# breakout-a-bit.net
KiCad netlist of a schematic drawn in EAGLE
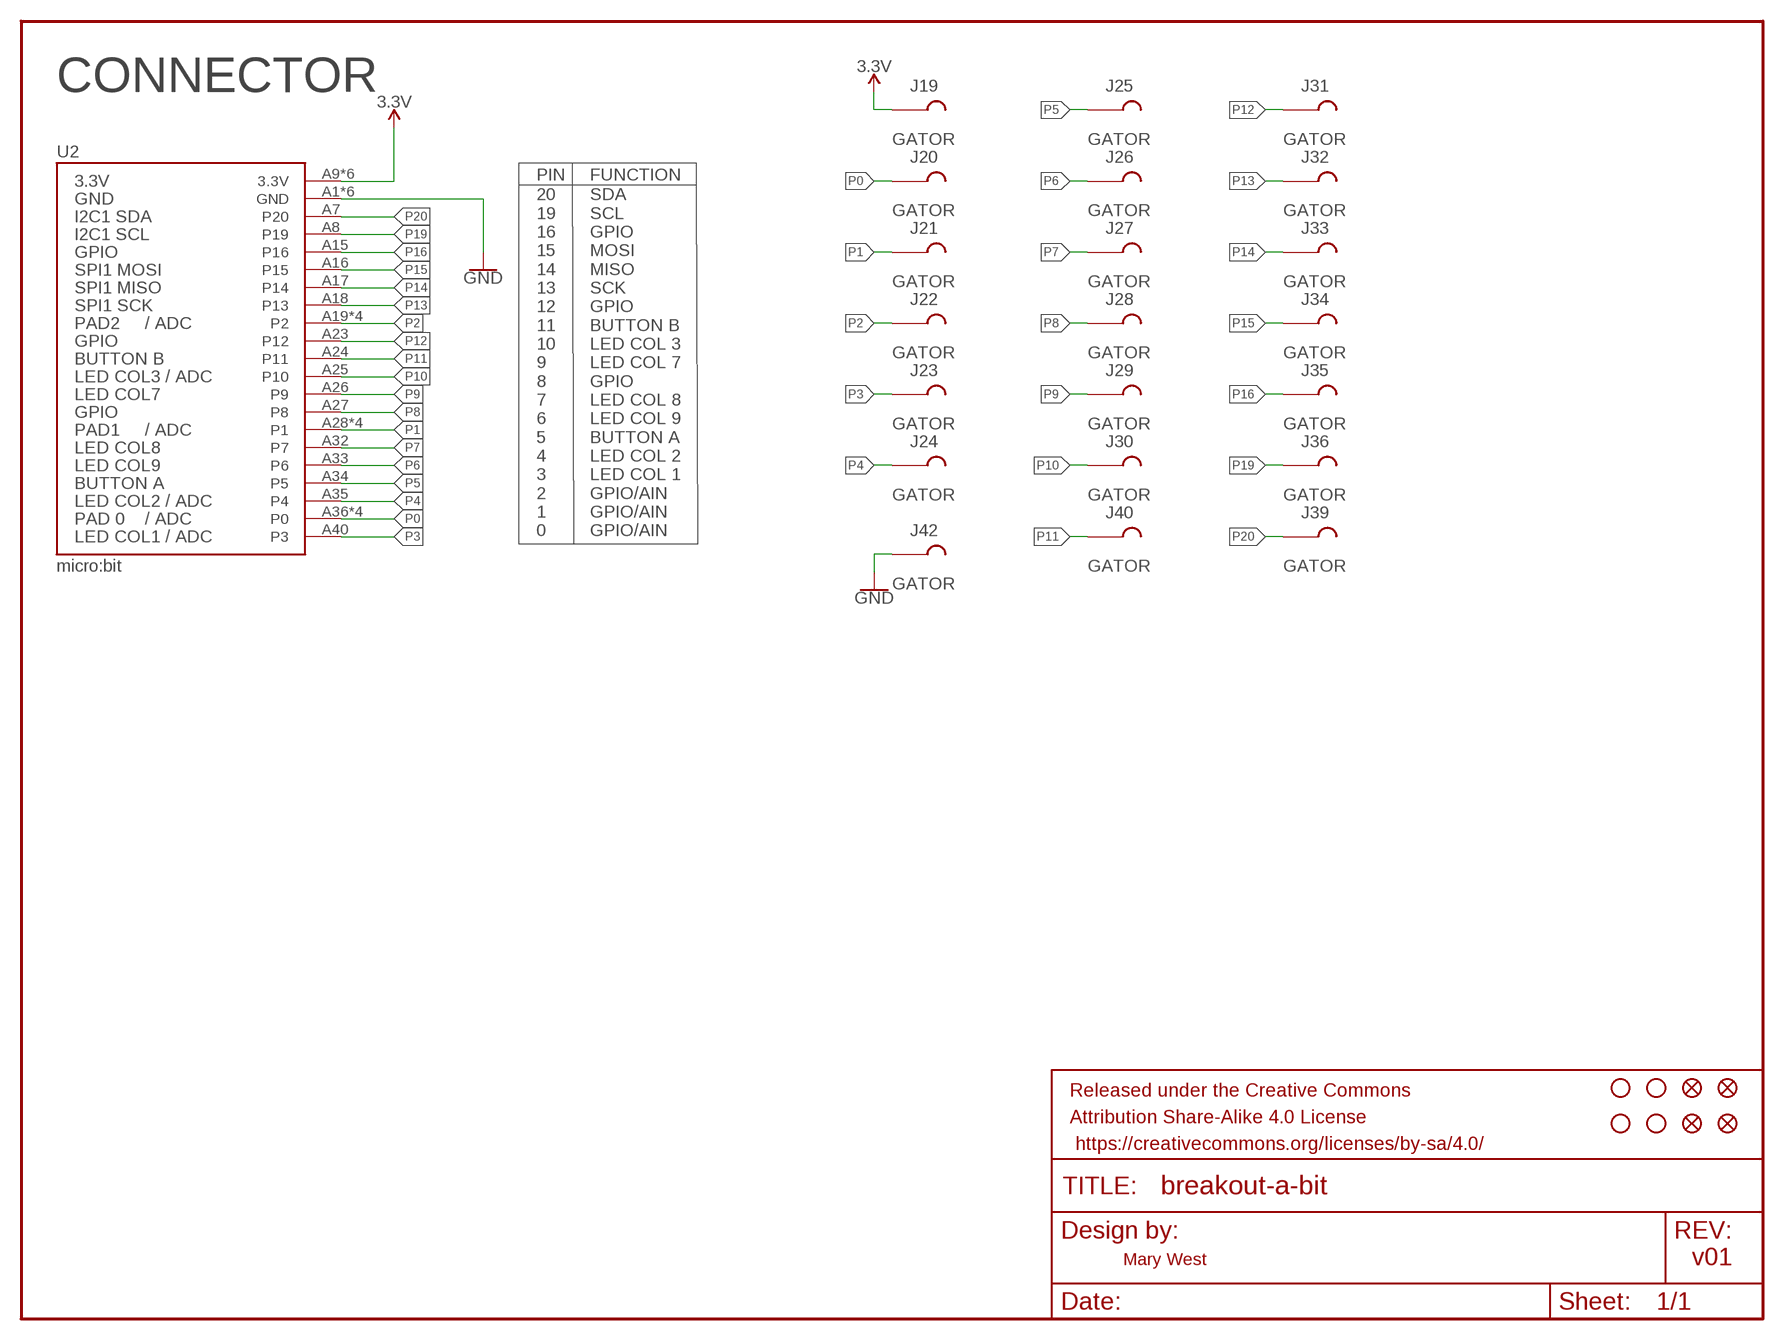
[diagram p0: schematic, sheet 1]

(export (version "E")
  (design (tool "Eeschema 10.0.6"))
  (components
    (comp (ref "FD1")
      (value "FIDUCIAL1X2")
      (footprint "eagle-import:FIDUCIAL-1X2")
      (libsource (lib "eagle-import") (part "FIDUCIAL1X2"))
    )
    (comp (ref "FD2")
      (value "FIDUCIAL1X2")
      (footprint "eagle-import:FIDUCIAL-1X2")
      (libsource (lib "eagle-import") (part "FIDUCIAL1X2"))
    )
    (comp (ref "FD3")
      (value "FIDUCIAL1X2")
      (footprint "eagle-import:FIDUCIAL-1X2")
      (libsource (lib "eagle-import") (part "FIDUCIAL1X2"))
    )
    (comp (ref "FD4")
      (value "FIDUCIAL1X2")
      (footprint "eagle-import:FIDUCIAL-1X2")
      (libsource (lib "eagle-import") (part "FIDUCIAL1X2"))
    )
    (comp (ref "FRAME1")
      (value "FRAME-LETTER")
      (footprint "eagle-import:CREATIVE_COMMONS")
      (libsource (lib "eagle-import") (part "FRAME-LETTER"))
    )
    (comp (ref "H1")
      (value "STAND-OFF")
      (footprint "eagle-import:STAND-OFF")
      (libsource (lib "eagle-import") (part "STAND-OFF"))
    )
    (comp (ref "H2")
      (value "STAND-OFF")
      (footprint "eagle-import:STAND-OFF")
      (libsource (lib "eagle-import") (part "STAND-OFF"))
    )
    (comp (ref "H3")
      (value "STAND-OFF")
      (footprint "eagle-import:STAND-OFF")
      (libsource (lib "eagle-import") (part "STAND-OFF"))
    )
    (comp (ref "H4")
      (value "STAND-OFF")
      (footprint "eagle-import:STAND-OFF")
      (libsource (lib "eagle-import") (part "STAND-OFF"))
    )
    (comp (ref "J19")
      (value "GATOR")
      (footprint "eagle-import:GATOR")
      (libsource (lib "eagle-import") (part "GATOR"))
    )
    (comp (ref "J20")
      (value "GATOR")
      (footprint "eagle-import:GATOR")
      (libsource (lib "eagle-import") (part "GATOR"))
    )
    (comp (ref "J21")
      (value "GATOR")
      (footprint "eagle-import:GATOR")
      (libsource (lib "eagle-import") (part "GATOR"))
    )
    (comp (ref "J22")
      (value "GATOR")
      (footprint "eagle-import:GATOR")
      (libsource (lib "eagle-import") (part "GATOR"))
    )
    (comp (ref "J23")
      (value "GATOR")
      (footprint "eagle-import:GATOR")
      (libsource (lib "eagle-import") (part "GATOR"))
    )
    (comp (ref "J24")
      (value "GATOR")
      (footprint "eagle-import:GATOR")
      (libsource (lib "eagle-import") (part "GATOR"))
    )
    (comp (ref "J25")
      (value "GATOR")
      (footprint "eagle-import:GATOR")
      (libsource (lib "eagle-import") (part "GATOR"))
    )
    (comp (ref "J26")
      (value "GATOR")
      (footprint "eagle-import:GATOR")
      (libsource (lib "eagle-import") (part "GATOR"))
    )
    (comp (ref "J27")
      (value "GATOR")
      (footprint "eagle-import:GATOR")
      (libsource (lib "eagle-import") (part "GATOR"))
    )
    (comp (ref "J28")
      (value "GATOR")
      (footprint "eagle-import:GATOR")
      (libsource (lib "eagle-import") (part "GATOR"))
    )
    (comp (ref "J29")
      (value "GATOR")
      (footprint "eagle-import:GATOR")
      (libsource (lib "eagle-import") (part "GATOR"))
    )
    (comp (ref "J30")
      (value "GATOR")
      (footprint "eagle-import:GATOR")
      (libsource (lib "eagle-import") (part "GATOR"))
    )
    (comp (ref "J31")
      (value "GATOR")
      (footprint "eagle-import:GATOR")
      (libsource (lib "eagle-import") (part "GATOR"))
    )
    (comp (ref "J32")
      (value "GATOR")
      (footprint "eagle-import:GATOR")
      (libsource (lib "eagle-import") (part "GATOR"))
    )
    (comp (ref "J33")
      (value "GATOR")
      (footprint "eagle-import:GATOR")
      (libsource (lib "eagle-import") (part "GATOR"))
    )
    (comp (ref "J34")
      (value "GATOR")
      (footprint "eagle-import:GATOR")
      (libsource (lib "eagle-import") (part "GATOR"))
    )
    (comp (ref "J35")
      (value "GATOR")
      (footprint "eagle-import:GATOR")
      (libsource (lib "eagle-import") (part "GATOR"))
    )
    (comp (ref "J36")
      (value "GATOR")
      (footprint "eagle-import:GATOR")
      (libsource (lib "eagle-import") (part "GATOR"))
    )
    (comp (ref "J39")
      (value "GATOR")
      (footprint "eagle-import:GATOR")
      (libsource (lib "eagle-import") (part "GATOR"))
    )
    (comp (ref "J40")
      (value "GATOR")
      (footprint "eagle-import:GATOR")
      (libsource (lib "eagle-import") (part "GATOR"))
    )
    (comp (ref "J42")
      (value "GATOR")
      (footprint "eagle-import:GATOR")
      (libsource (lib "eagle-import") (part "GATOR"))
    )
    (comp (ref "U2")
      (value "micro:bit")
      (footprint "eagle-import:MICRO_BIT_RA_PTH")
      (libsource (lib "eagle-import") (part "MICRO{colon}BITLEDS_UP"))
    )
  )
  (nets
    (net (code "1") (name "3.3V") (class "Default")
      (node (ref "J19") (pin "P$1") (pinfunction "P$1_P$1") (pintype "bidirectional"))
      (node (ref "U2") (pin "A10") (pinfunction "3.3V_A10") (pintype "bidirectional"))
      (node (ref "U2") (pin "A11") (pinfunction "3.3V_A11") (pintype "bidirectional"))
      (node (ref "U2") (pin "A12") (pinfunction "3.3V_A12") (pintype "bidirectional"))
      (node (ref "U2") (pin "A13") (pinfunction "3.3V_A13") (pintype "bidirectional"))
      (node (ref "U2") (pin "A14") (pinfunction "3.3V_A14") (pintype "bidirectional"))
      (node (ref "U2") (pin "A9") (pinfunction "3.3V_A9") (pintype "bidirectional"))
    )
    (net (code "2") (name "GND") (class "Default")
      (node (ref "J42") (pin "P$1") (pinfunction "P$1_P$1") (pintype "bidirectional"))
      (node (ref "U2") (pin "A1") (pinfunction "GND_A1") (pintype "bidirectional"))
      (node (ref "U2") (pin "A2") (pinfunction "GND_A2") (pintype "bidirectional"))
      (node (ref "U2") (pin "A3") (pinfunction "GND_A3") (pintype "bidirectional"))
      (node (ref "U2") (pin "A4") (pinfunction "GND_A4") (pintype "bidirectional"))
      (node (ref "U2") (pin "A5") (pinfunction "GND_A5") (pintype "bidirectional"))
      (node (ref "U2") (pin "A6") (pinfunction "GND_A6") (pintype "bidirectional"))
    )
    (net (code "3") (name "P0") (class "Default")
      (node (ref "J20") (pin "P$1") (pinfunction "P$1_P$1") (pintype "bidirectional"))
      (node (ref "U2") (pin "A36") (pinfunction "P0_A36") (pintype "bidirectional"))
      (node (ref "U2") (pin "A37") (pinfunction "P0_A37") (pintype "bidirectional"))
      (node (ref "U2") (pin "A38") (pinfunction "P0_A38") (pintype "bidirectional"))
      (node (ref "U2") (pin "A39") (pinfunction "P0_A39") (pintype "bidirectional"))
    )
    (net (code "4") (name "P1") (class "Default")
      (node (ref "J21") (pin "P$1") (pinfunction "P$1_P$1") (pintype "bidirectional"))
      (node (ref "U2") (pin "A28") (pinfunction "P1_A28") (pintype "bidirectional"))
      (node (ref "U2") (pin "A29") (pinfunction "P1_A29") (pintype "bidirectional"))
      (node (ref "U2") (pin "A30") (pinfunction "P1_A30") (pintype "bidirectional"))
      (node (ref "U2") (pin "A31") (pinfunction "P1_A31") (pintype "bidirectional"))
    )
    (net (code "5") (name "P2") (class "Default")
      (node (ref "J22") (pin "P$1") (pinfunction "P$1_P$1") (pintype "bidirectional"))
      (node (ref "U2") (pin "A19") (pinfunction "P2_A19") (pintype "bidirectional"))
      (node (ref "U2") (pin "A20") (pinfunction "P2_A20") (pintype "bidirectional"))
      (node (ref "U2") (pin "A21") (pinfunction "P2_A21") (pintype "bidirectional"))
      (node (ref "U2") (pin "A22") (pinfunction "P2_A22") (pintype "bidirectional"))
    )
    (net (code "6") (name "P3") (class "Default")
      (node (ref "J23") (pin "P$1") (pinfunction "P$1_P$1") (pintype "bidirectional"))
      (node (ref "U2") (pin "A40") (pinfunction "P3_A40") (pintype "bidirectional"))
    )
    (net (code "7") (name "P4") (class "Default")
      (node (ref "J24") (pin "P$1") (pinfunction "P$1_P$1") (pintype "bidirectional"))
      (node (ref "U2") (pin "A35") (pinfunction "P4_A35") (pintype "bidirectional"))
    )
    (net (code "8") (name "P5") (class "Default")
      (node (ref "J25") (pin "P$1") (pinfunction "P$1_P$1") (pintype "bidirectional"))
      (node (ref "U2") (pin "A34") (pinfunction "P5_A34") (pintype "bidirectional"))
    )
    (net (code "9") (name "P6") (class "Default")
      (node (ref "J26") (pin "P$1") (pinfunction "P$1_P$1") (pintype "bidirectional"))
      (node (ref "U2") (pin "A33") (pinfunction "P6_A33") (pintype "bidirectional"))
    )
    (net (code "10") (name "P7") (class "Default")
      (node (ref "J27") (pin "P$1") (pinfunction "P$1_P$1") (pintype "bidirectional"))
      (node (ref "U2") (pin "A32") (pinfunction "P7_A32") (pintype "bidirectional"))
    )
    (net (code "11") (name "P8") (class "Default")
      (node (ref "J28") (pin "P$1") (pinfunction "P$1_P$1") (pintype "bidirectional"))
      (node (ref "U2") (pin "A27") (pinfunction "P8_A27") (pintype "bidirectional"))
    )
    (net (code "12") (name "P9") (class "Default")
      (node (ref "J29") (pin "P$1") (pinfunction "P$1_P$1") (pintype "bidirectional"))
      (node (ref "U2") (pin "A26") (pinfunction "P9_A26") (pintype "bidirectional"))
    )
    (net (code "13") (name "P10") (class "Default")
      (node (ref "J30") (pin "P$1") (pinfunction "P$1_P$1") (pintype "bidirectional"))
      (node (ref "U2") (pin "A25") (pinfunction "P10_A25") (pintype "bidirectional"))
    )
    (net (code "14") (name "P11") (class "Default")
      (node (ref "J40") (pin "P$1") (pinfunction "P$1_P$1") (pintype "bidirectional"))
      (node (ref "U2") (pin "A24") (pinfunction "P11_A24") (pintype "bidirectional"))
    )
    (net (code "15") (name "P12") (class "Default")
      (node (ref "J31") (pin "P$1") (pinfunction "P$1_P$1") (pintype "bidirectional"))
      (node (ref "U2") (pin "A23") (pinfunction "P12_A23") (pintype "bidirectional"))
    )
    (net (code "16") (name "P13") (class "Default")
      (node (ref "J32") (pin "P$1") (pinfunction "P$1_P$1") (pintype "bidirectional"))
      (node (ref "U2") (pin "A18") (pinfunction "P13_A18") (pintype "bidirectional"))
    )
    (net (code "17") (name "P14") (class "Default")
      (node (ref "J33") (pin "P$1") (pinfunction "P$1_P$1") (pintype "bidirectional"))
      (node (ref "U2") (pin "A17") (pinfunction "P14_A17") (pintype "bidirectional"))
    )
    (net (code "18") (name "P15") (class "Default")
      (node (ref "J34") (pin "P$1") (pinfunction "P$1_P$1") (pintype "bidirectional"))
      (node (ref "U2") (pin "A16") (pinfunction "P15_A16") (pintype "bidirectional"))
    )
    (net (code "19") (name "P16") (class "Default")
      (node (ref "J35") (pin "P$1") (pinfunction "P$1_P$1") (pintype "bidirectional"))
      (node (ref "U2") (pin "A15") (pinfunction "P16_A15") (pintype "bidirectional"))
    )
    (net (code "20") (name "P19") (class "Default")
      (node (ref "J36") (pin "P$1") (pinfunction "P$1_P$1") (pintype "bidirectional"))
      (node (ref "U2") (pin "A8") (pinfunction "P19_A8") (pintype "bidirectional"))
    )
    (net (code "21") (name "P20") (class "Default")
      (node (ref "J39") (pin "P$1") (pinfunction "P$1_P$1") (pintype "bidirectional"))
      (node (ref "U2") (pin "A7") (pinfunction "P20_A7") (pintype "bidirectional"))
    )
  )
)
